# INV_1_0.net
KiCad netlist of a schematic drawn in EAGLE
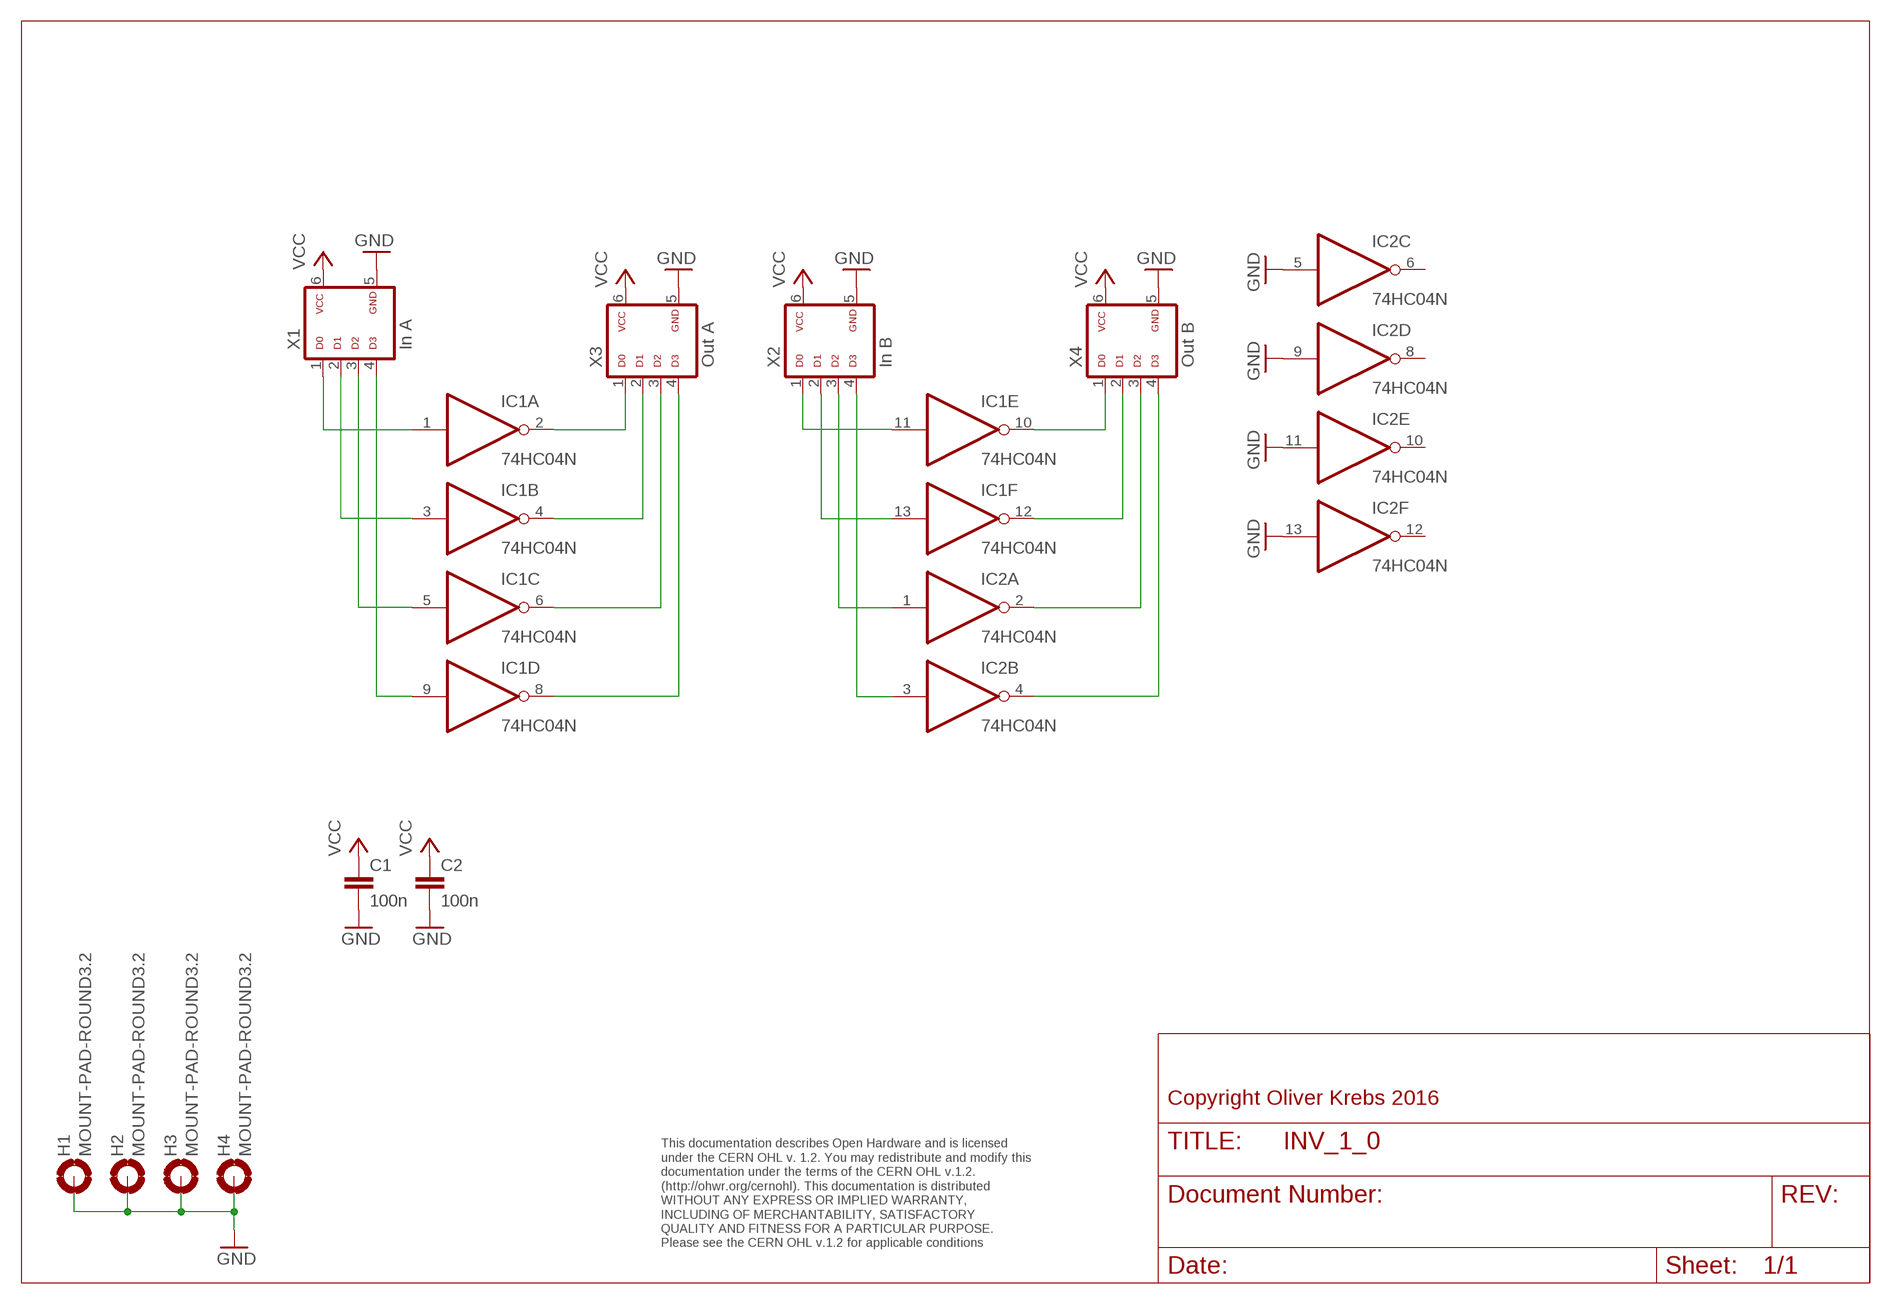
[diagram p0: schematic, sheet 1]

(export (version "E")
  (design (tool "Eeschema 10.0.6"))
  (components
    (comp (ref "C1")
      (value "100n")
      (footprint "eagle-import:C050-025X075")
      (libsource (lib "eagle-import") (part "C-EU050-025X075"))
    )
    (comp (ref "C2")
      (value "100n")
      (footprint "eagle-import:C050-025X075")
      (libsource (lib "eagle-import") (part "C-EU050-025X075"))
    )
    (comp (ref "H1")
      (value "MOUNT-PAD-ROUND3.2")
      (footprint "eagle-import:3,2-PAD")
      (libsource (lib "eagle-import") (part "MOUNT-PAD-ROUND3.2"))
    )
    (comp (ref "H2")
      (value "MOUNT-PAD-ROUND3.2")
      (footprint "eagle-import:3,2-PAD")
      (libsource (lib "eagle-import") (part "MOUNT-PAD-ROUND3.2"))
    )
    (comp (ref "H3")
      (value "MOUNT-PAD-ROUND3.2")
      (footprint "eagle-import:3,2-PAD")
      (libsource (lib "eagle-import") (part "MOUNT-PAD-ROUND3.2"))
    )
    (comp (ref "H4")
      (value "MOUNT-PAD-ROUND3.2")
      (footprint "eagle-import:3,2-PAD")
      (libsource (lib "eagle-import") (part "MOUNT-PAD-ROUND3.2"))
    )
    (comp (ref "IC1")
      (value "74HC04N")
      (footprint "eagle-import:DIL14")
      (libsource (lib "eagle-import") (part "7404NHC"))
    )
    (comp (ref "IC2")
      (value "74HC04N")
      (footprint "eagle-import:DIL14")
      (libsource (lib "eagle-import") (part "7404NHC"))
    )
    (comp (ref "X1")
      (value "In A")
      (footprint "eagle-import:ML-6")
      (libsource (lib "eagle-import") (part "ML6D"))
    )
    (comp (ref "X2")
      (value "In B")
      (footprint "eagle-import:ML-6")
      (libsource (lib "eagle-import") (part "ML6D"))
    )
    (comp (ref "X3")
      (value "Out A")
      (footprint "eagle-import:ML-6")
      (libsource (lib "eagle-import") (part "ML6D"))
    )
    (comp (ref "X4")
      (value "Out B")
      (footprint "eagle-import:ML-6")
      (libsource (lib "eagle-import") (part "ML6D"))
    )
  )
  (nets
    (net (code "1") (name "GND") (class "Default")
      (node (ref "C1") (pin "2") (pinfunction "2_2") (pintype "passive"))
      (node (ref "C2") (pin "2") (pinfunction "2_2") (pintype "passive"))
      (node (ref "H1") (pin "B3,2") (pinfunction "MOUNT_B3,2") (pintype "passive"))
      (node (ref "H2") (pin "B3,2") (pinfunction "MOUNT_B3,2") (pintype "passive"))
      (node (ref "H3") (pin "B3,2") (pinfunction "MOUNT_B3,2") (pintype "passive"))
      (node (ref "H4") (pin "B3,2") (pinfunction "MOUNT_B3,2") (pintype "passive"))
      (node (ref "IC2") (pin "11") (pinfunction "I_11") (pintype "input"))
      (node (ref "IC2") (pin "13") (pinfunction "I_13") (pintype "input"))
      (node (ref "IC2") (pin "5") (pinfunction "I_5") (pintype "input"))
      (node (ref "IC2") (pin "9") (pinfunction "I_9") (pintype "input"))
      (node (ref "X1") (pin "5") (pinfunction "5_5") (pintype "passive"))
      (node (ref "X2") (pin "5") (pinfunction "5_5") (pintype "passive"))
      (node (ref "X3") (pin "5") (pinfunction "5_5") (pintype "passive"))
      (node (ref "X4") (pin "5") (pinfunction "5_5") (pintype "passive"))
    )
    (net (code "2") (name "Net-(IC1A-I)") (class "Default")
      (node (ref "IC1") (pin "1") (pinfunction "I_1") (pintype "input"))
      (node (ref "X1") (pin "1") (pinfunction "1_1") (pintype "passive"))
    )
    (net (code "3") (name "Net-(IC1A-O)") (class "Default")
      (node (ref "IC1") (pin "2") (pinfunction "O_2") (pintype "output"))
      (node (ref "X3") (pin "1") (pinfunction "1_1") (pintype "passive"))
    )
    (net (code "4") (name "Net-(IC1B-I)") (class "Default")
      (node (ref "IC1") (pin "3") (pinfunction "I_3") (pintype "input"))
      (node (ref "X1") (pin "2") (pinfunction "2_2") (pintype "passive"))
    )
    (net (code "5") (name "Net-(IC1B-O)") (class "Default")
      (node (ref "IC1") (pin "4") (pinfunction "O_4") (pintype "output"))
      (node (ref "X3") (pin "2") (pinfunction "2_2") (pintype "passive"))
    )
    (net (code "6") (name "Net-(IC1C-I)") (class "Default")
      (node (ref "IC1") (pin "5") (pinfunction "I_5") (pintype "input"))
      (node (ref "X1") (pin "3") (pinfunction "3_3") (pintype "passive"))
    )
    (net (code "7") (name "Net-(IC1C-O)") (class "Default")
      (node (ref "IC1") (pin "6") (pinfunction "O_6") (pintype "output"))
      (node (ref "X3") (pin "3") (pinfunction "3_3") (pintype "passive"))
    )
    (net (code "8") (name "Net-(IC1D-I)") (class "Default")
      (node (ref "IC1") (pin "9") (pinfunction "I_9") (pintype "input"))
      (node (ref "X1") (pin "4") (pinfunction "4_4") (pintype "passive"))
    )
    (net (code "9") (name "Net-(IC1D-O)") (class "Default")
      (node (ref "IC1") (pin "8") (pinfunction "O_8") (pintype "output"))
      (node (ref "X3") (pin "4") (pinfunction "4_4") (pintype "passive"))
    )
    (net (code "10") (name "Net-(IC1E-I)") (class "Default")
      (node (ref "IC1") (pin "11") (pinfunction "I_11") (pintype "input"))
      (node (ref "X2") (pin "1") (pinfunction "1_1") (pintype "passive"))
    )
    (net (code "11") (name "Net-(IC1E-O)") (class "Default")
      (node (ref "IC1") (pin "10") (pinfunction "O_10") (pintype "output"))
      (node (ref "X4") (pin "1") (pinfunction "1_1") (pintype "passive"))
    )
    (net (code "12") (name "Net-(IC1F-I)") (class "Default")
      (node (ref "IC1") (pin "13") (pinfunction "I_13") (pintype "input"))
      (node (ref "X2") (pin "2") (pinfunction "2_2") (pintype "passive"))
    )
    (net (code "13") (name "Net-(IC1F-O)") (class "Default")
      (node (ref "IC1") (pin "12") (pinfunction "O_12") (pintype "output"))
      (node (ref "X4") (pin "2") (pinfunction "2_2") (pintype "passive"))
    )
    (net (code "14") (name "Net-(IC2A-I)") (class "Default")
      (node (ref "IC2") (pin "1") (pinfunction "I_1") (pintype "input"))
      (node (ref "X2") (pin "3") (pinfunction "3_3") (pintype "passive"))
    )
    (net (code "15") (name "Net-(IC2A-O)") (class "Default")
      (node (ref "IC2") (pin "2") (pinfunction "O_2") (pintype "output"))
      (node (ref "X4") (pin "3") (pinfunction "3_3") (pintype "passive"))
    )
    (net (code "16") (name "Net-(IC2B-I)") (class "Default")
      (node (ref "IC2") (pin "3") (pinfunction "I_3") (pintype "input"))
      (node (ref "X2") (pin "4") (pinfunction "4_4") (pintype "passive"))
    )
    (net (code "17") (name "Net-(IC2B-O)") (class "Default")
      (node (ref "IC2") (pin "4") (pinfunction "O_4") (pintype "output"))
      (node (ref "X4") (pin "4") (pinfunction "4_4") (pintype "passive"))
    )
    (net (code "18") (name "VCC") (class "Default")
      (node (ref "C1") (pin "1") (pinfunction "1_1") (pintype "passive"))
      (node (ref "C2") (pin "1") (pinfunction "1_1") (pintype "passive"))
      (node (ref "X1") (pin "6") (pinfunction "6_6") (pintype "passive"))
      (node (ref "X2") (pin "6") (pinfunction "6_6") (pintype "passive"))
      (node (ref "X3") (pin "6") (pinfunction "6_6") (pintype "passive"))
      (node (ref "X4") (pin "6") (pinfunction "6_6") (pintype "passive"))
    )
    (net (code "19") (name "unconnected-(IC2C-O-Pad6)") (class "Default")
      (node (ref "IC2") (pin "6") (pinfunction "O_6") (pintype "output"))
    )
    (net (code "20") (name "unconnected-(IC2D-O-Pad8)") (class "Default")
      (node (ref "IC2") (pin "8") (pinfunction "O_8") (pintype "output"))
    )
    (net (code "21") (name "unconnected-(IC2E-O-Pad10)") (class "Default")
      (node (ref "IC2") (pin "10") (pinfunction "O_10") (pintype "output"))
    )
    (net (code "22") (name "unconnected-(IC2F-O-Pad12)") (class "Default")
      (node (ref "IC2") (pin "12") (pinfunction "O_12") (pintype "output"))
    )
  )
)
